# ausbee_carte_alim.net
KiCad netlist of a schematic drawn in EAGLE
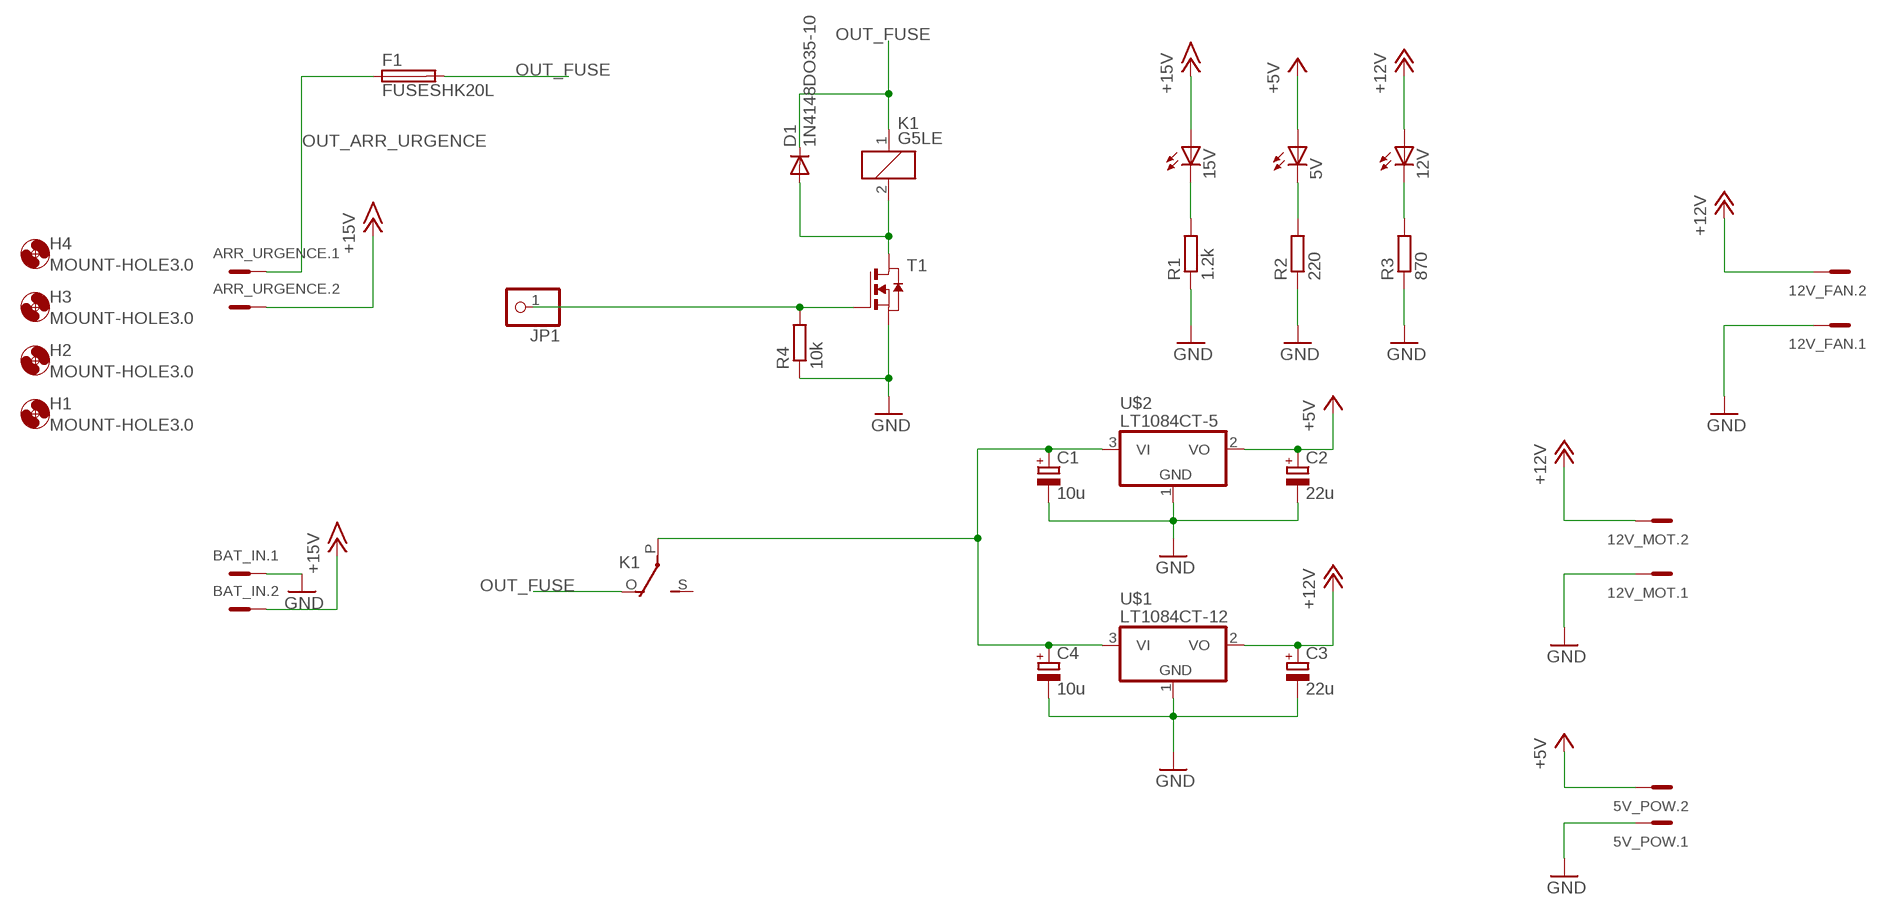
[diagram p0: schematic, sheet 1]

(export (version "E")
  (design (tool "Eeschema 10.0.6"))
  (components
    (comp (ref "5V")
      (value "LED3MM")
      (footprint "eagle-import:LED3MM")
      (libsource (lib "eagle-import") (part "LED3MM"))
    )
    (comp (ref "5V_POW")
      (value "MCV2")
      (footprint "eagle-import:MCV2")
      (libsource (lib "eagle-import") (part "MCV2"))
    )
    (comp (ref "12V")
      (value "LED3MM")
      (footprint "eagle-import:LED3MM")
      (libsource (lib "eagle-import") (part "LED3MM"))
    )
    (comp (ref "12V_FAN")
      (value "MCV2")
      (footprint "eagle-import:MCV2")
      (libsource (lib "eagle-import") (part "MCV2"))
    )
    (comp (ref "12V_MOT")
      (value "MCV2")
      (footprint "eagle-import:MCV2")
      (libsource (lib "eagle-import") (part "MCV2"))
    )
    (comp (ref "15V")
      (value "LED3MM")
      (footprint "eagle-import:LED3MM")
      (libsource (lib "eagle-import") (part "LED3MM"))
    )
    (comp (ref "ARR_URGENCE")
      (value "MCV2")
      (footprint "eagle-import:MCV2")
      (libsource (lib "eagle-import") (part "MCV2"))
    )
    (comp (ref "BAT_IN")
      (value "MCV2")
      (footprint "eagle-import:MCV2")
      (libsource (lib "eagle-import") (part "MCV2"))
    )
    (comp (ref "C1")
      (value "10u")
      (footprint "eagle-import:E5-8,5")
      (libsource (lib "eagle-import") (part "CPOL-EUE5-8.5"))
    )
    (comp (ref "C2")
      (value "22u")
      (footprint "eagle-import:CT7343")
      (libsource (lib "eagle-import") (part "CPOL-EUCT7343"))
    )
    (comp (ref "C3")
      (value "22u")
      (footprint "eagle-import:CT7343")
      (libsource (lib "eagle-import") (part "CPOL-EUCT7343"))
    )
    (comp (ref "C4")
      (value "10u")
      (footprint "eagle-import:E5-8,5")
      (libsource (lib "eagle-import") (part "CPOL-EUE5-8.5"))
    )
    (comp (ref "D1")
      (value "1N4148DO35-10")
      (footprint "eagle-import:DO35-10")
      (libsource (lib "eagle-import") (part "1N4148DO35-10"))
    )
    (comp (ref "F1")
      (value "FUSESHK20L")
      (footprint "eagle-import:SHK20L")
      (libsource (lib "eagle-import") (part "FUSESHK20L"))
    )
    (comp (ref "H1")
      (value "MOUNT-HOLE3.0")
      (footprint "eagle-import:3,0")
      (libsource (lib "eagle-import") (part "MOUNT-HOLE3.0"))
    )
    (comp (ref "H2")
      (value "MOUNT-HOLE3.0")
      (footprint "eagle-import:3,0")
      (libsource (lib "eagle-import") (part "MOUNT-HOLE3.0"))
    )
    (comp (ref "H3")
      (value "MOUNT-HOLE3.0")
      (footprint "eagle-import:3,0")
      (libsource (lib "eagle-import") (part "MOUNT-HOLE3.0"))
    )
    (comp (ref "H4")
      (value "MOUNT-HOLE3.0")
      (footprint "eagle-import:3,0")
      (libsource (lib "eagle-import") (part "MOUNT-HOLE3.0"))
    )
    (comp (ref "JP1")
      (value "PINHD-1X1")
      (footprint "eagle-import:1X01")
      (libsource (lib "eagle-import") (part "PINHD-1X1"))
    )
    (comp (ref "K1")
      (value "G5LE")
      (footprint "eagle-import:G5LE")
      (libsource (lib "eagle-import") (part "G5LE"))
    )
    (comp (ref "R1")
      (value "1.2k")
      (footprint "eagle-import:0309V")
      (libsource (lib "eagle-import") (part "R-EU_0309/V"))
    )
    (comp (ref "R2")
      (value "220")
      (footprint "eagle-import:0309V")
      (libsource (lib "eagle-import") (part "R-EU_0309/V"))
    )
    (comp (ref "R3")
      (value "870")
      (footprint "eagle-import:0309V")
      (libsource (lib "eagle-import") (part "R-EU_0309/V"))
    )
    (comp (ref "R4")
      (value "10k")
      (footprint "eagle-import:0309V")
      (libsource (lib "eagle-import") (part "R-EU_0309/V"))
    )
    (comp (ref "T1")
      (value "NMOSSOT23")
      (footprint "eagle-import:SOT-23")
      (libsource (lib "eagle-import") (part "NMOSSOT23"))
    )
    (comp (ref "U$1")
      (value "LT1084CT-12")
      (footprint "eagle-import:TO220V")
      (libsource (lib "eagle-import") (part "LT1084CT-12"))
    )
    (comp (ref "U$2")
      (value "LT1084CT-5")
      (footprint "eagle-import:TO220V")
      (libsource (lib "eagle-import") (part "LT1084CT-5"))
    )
  )
  (nets
    (net (code "1") (name "+5V") (class "Default")
      (node (ref "5V") (pin "A") (pinfunction "A_A") (pintype "passive"))
      (node (ref "5V_POW") (pin "2") (pinfunction "SK_2") (pintype "passive"))
      (node (ref "C2") (pin "+") (pinfunction "+_+") (pintype "passive"))
      (node (ref "U$2") (pin "2") (pinfunction "VO_2") (pintype "passive"))
    )
    (net (code "2") (name "+12V") (class "Default")
      (node (ref "12V") (pin "A") (pinfunction "A_A") (pintype "passive"))
      (node (ref "12V_FAN") (pin "2") (pinfunction "SK_2") (pintype "passive"))
      (node (ref "12V_MOT") (pin "2") (pinfunction "SK_2") (pintype "passive"))
      (node (ref "C3") (pin "+") (pinfunction "+_+") (pintype "passive"))
      (node (ref "U$1") (pin "2") (pinfunction "VO_2") (pintype "passive"))
    )
    (net (code "3") (name "+15V") (class "Default")
      (node (ref "15V") (pin "A") (pinfunction "A_A") (pintype "passive"))
      (node (ref "ARR_URGENCE") (pin "2") (pinfunction "SK_2") (pintype "passive"))
      (node (ref "BAT_IN") (pin "2") (pinfunction "SK_2") (pintype "passive"))
    )
    (net (code "4") (name "/OUT_ARR_URGENCE") (class "Default")
      (node (ref "ARR_URGENCE") (pin "1") (pinfunction "SK_1") (pintype "passive"))
      (node (ref "F1") (pin "1A") (pinfunction "1_1A") (pintype "passive"))
    )
    (net (code "5") (name "/OUT_FUSE") (class "Default")
      (node (ref "D1") (pin "C") (pinfunction "C_C") (pintype "passive"))
      (node (ref "F1") (pin "2A") (pinfunction "2_2A") (pintype "passive"))
      (node (ref "K1") (pin "1") (pinfunction "1_1") (pintype "passive"))
      (node (ref "K1") (pin "O") (pinfunction "O_O") (pintype "passive"))
    )
    (net (code "6") (name "GND") (class "Default")
      (node (ref "12V_FAN") (pin "1") (pinfunction "SK_1") (pintype "passive"))
      (node (ref "12V_MOT") (pin "1") (pinfunction "SK_1") (pintype "passive"))
      (node (ref "5V_POW") (pin "1") (pinfunction "SK_1") (pintype "passive"))
      (node (ref "BAT_IN") (pin "1") (pinfunction "SK_1") (pintype "passive"))
      (node (ref "C1") (pin "-") (pinfunction "-_-") (pintype "passive"))
      (node (ref "C2") (pin "-") (pinfunction "-_-") (pintype "passive"))
      (node (ref "C3") (pin "-") (pinfunction "-_-") (pintype "passive"))
      (node (ref "C4") (pin "-") (pinfunction "-_-") (pintype "passive"))
      (node (ref "R1") (pin "1") (pinfunction "1_1") (pintype "passive"))
      (node (ref "R2") (pin "1") (pinfunction "1_1") (pintype "passive"))
      (node (ref "R3") (pin "1") (pinfunction "1_1") (pintype "passive"))
      (node (ref "R4") (pin "1") (pinfunction "1_1") (pintype "passive"))
      (node (ref "T1") (pin "2") (pinfunction "S_2") (pintype "passive"))
      (node (ref "U$1") (pin "1") (pinfunction "GND_1") (pintype "passive"))
      (node (ref "U$2") (pin "1") (pinfunction "GND_1") (pintype "passive"))
    )
    (net (code "7") (name "Net-(5V-C)") (class "Default")
      (node (ref "5V") (pin "K") (pinfunction "C_K") (pintype "passive"))
      (node (ref "R2") (pin "2") (pinfunction "2_2") (pintype "passive"))
    )
    (net (code "8") (name "Net-(12V-C)") (class "Default")
      (node (ref "12V") (pin "K") (pinfunction "C_K") (pintype "passive"))
      (node (ref "R3") (pin "2") (pinfunction "2_2") (pintype "passive"))
    )
    (net (code "9") (name "Net-(15V-C)") (class "Default")
      (node (ref "15V") (pin "K") (pinfunction "C_K") (pintype "passive"))
      (node (ref "R1") (pin "2") (pinfunction "2_2") (pintype "passive"))
    )
    (net (code "10") (name "Net-(T1-D)") (class "Default")
      (node (ref "D1") (pin "A") (pinfunction "A_A") (pintype "passive"))
      (node (ref "K1") (pin "2") (pinfunction "2_2") (pintype "passive"))
      (node (ref "T1") (pin "1") (pinfunction "D_1") (pintype "passive"))
    )
    (net (code "11") (name "Net-(T1-G)") (class "Default")
      (node (ref "JP1") (pin "1") (pinfunction "1_1") (pintype "passive"))
      (node (ref "R4") (pin "2") (pinfunction "2_2") (pintype "passive"))
      (node (ref "T1") (pin "3") (pinfunction "G_3") (pintype "passive"))
    )
    (net (code "12") (name "Net-(U$1-VI)") (class "Default")
      (node (ref "C1") (pin "+") (pinfunction "+_+") (pintype "passive"))
      (node (ref "C4") (pin "+") (pinfunction "+_+") (pintype "passive"))
      (node (ref "K1") (pin "P") (pinfunction "P_P") (pintype "passive"))
      (node (ref "U$1") (pin "3") (pinfunction "VI_3") (pintype "input"))
      (node (ref "U$2") (pin "3") (pinfunction "VI_3") (pintype "input"))
    )
    (net (code "13") (name "unconnected-(K1-PadS)") (class "Default")
      (node (ref "K1") (pin "S") (pinfunction "S_S") (pintype "passive"))
    )
  )
)
